# Rapide7seg.net
KiCad netlist of a schematic drawn in EAGLE
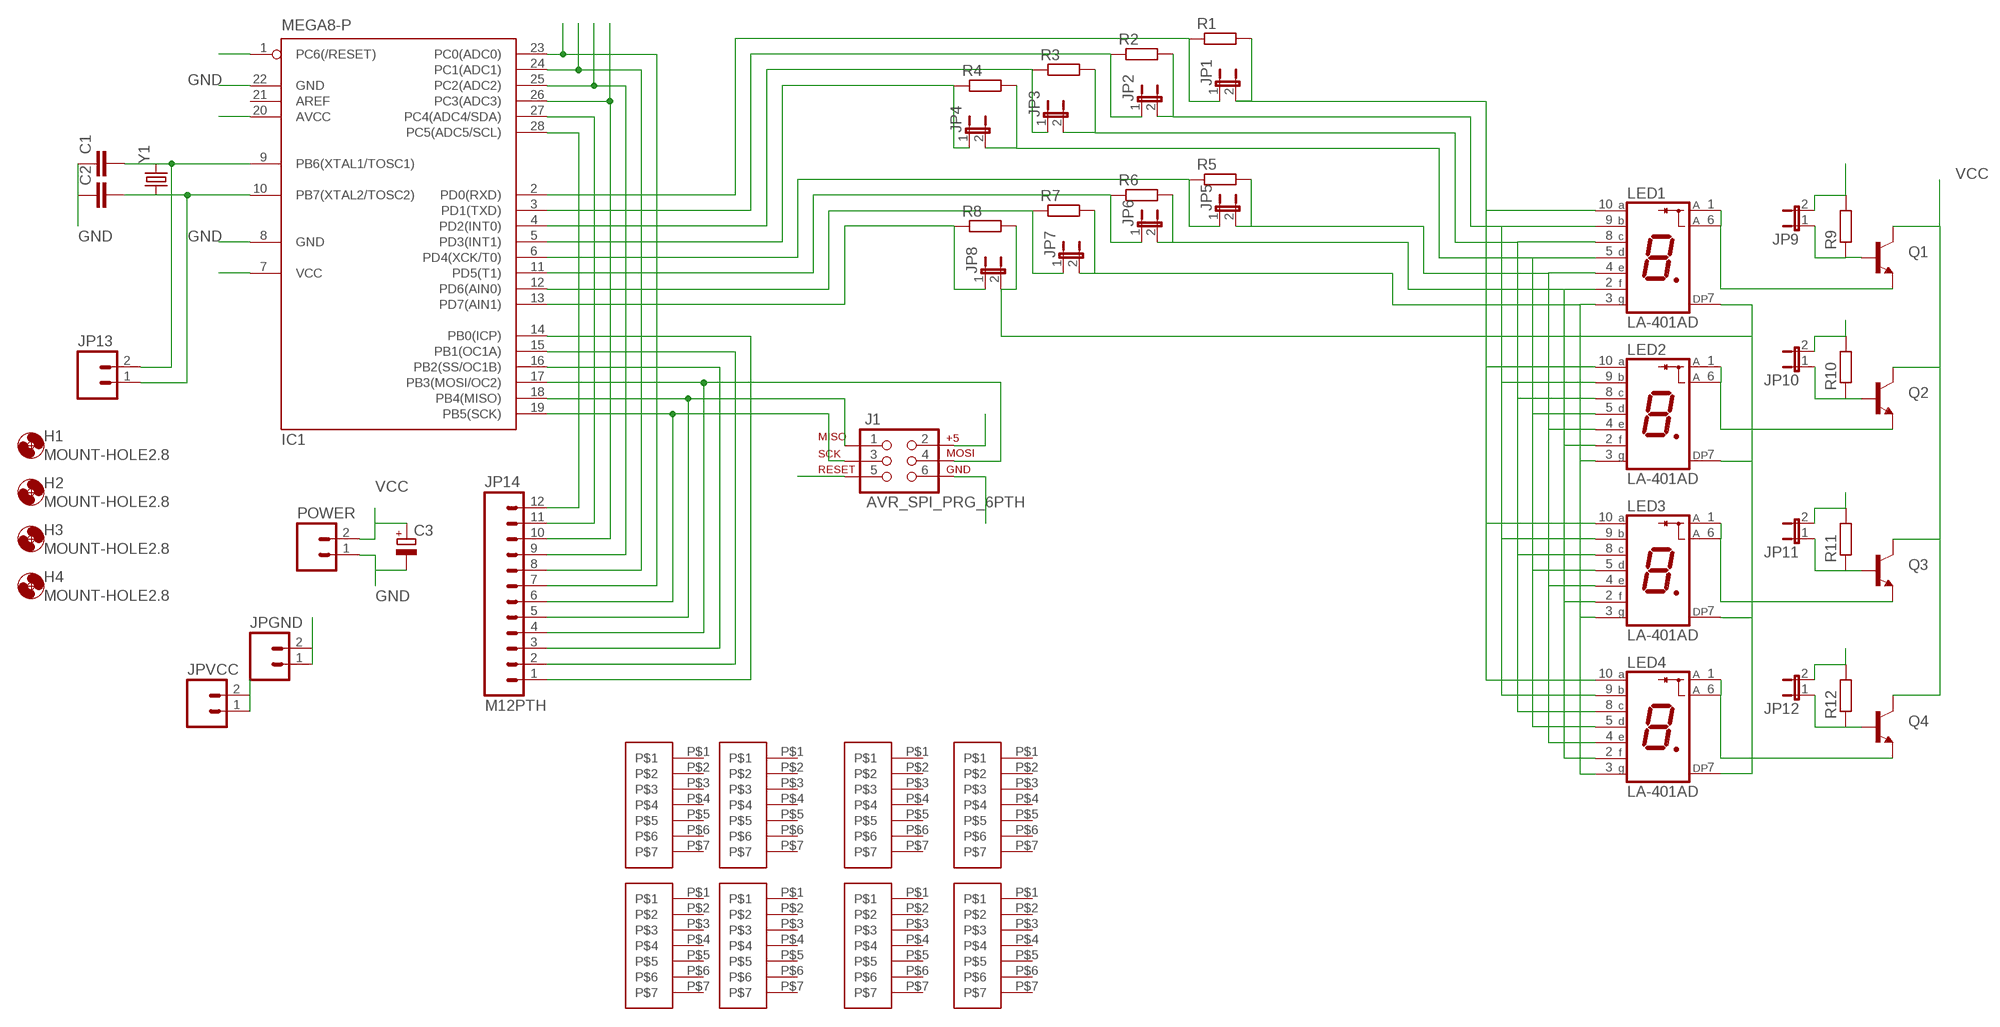
[diagram p0: schematic, sheet 1]

(export (version "E")
  (design (tool "Eeschema 10.0.6"))
  (components
    (comp (ref "C1")
      (value "C-EU025-024X044")
      (footprint "eagle-import:C025-024X044")
      (libsource (lib "eagle-import") (part "C-EU025-024X044"))
    )
    (comp (ref "C2")
      (value "C-EU025-024X044")
      (footprint "eagle-import:C025-024X044")
      (libsource (lib "eagle-import") (part "C-EU025-024X044"))
    )
    (comp (ref "C3")
      (value "CPOL-EUE1.8-4")
      (footprint "eagle-import:E1,8-4")
      (libsource (lib "eagle-import") (part "CPOL-EUE1.8-4"))
    )
    (comp (ref "H1")
      (value "MOUNT-HOLE2.8")
      (footprint "eagle-import:2,8")
      (libsource (lib "eagle-import") (part "MOUNT-HOLE2.8"))
    )
    (comp (ref "H2")
      (value "MOUNT-HOLE2.8")
      (footprint "eagle-import:2,8")
      (libsource (lib "eagle-import") (part "MOUNT-HOLE2.8"))
    )
    (comp (ref "H3")
      (value "MOUNT-HOLE2.8")
      (footprint "eagle-import:2,8")
      (libsource (lib "eagle-import") (part "MOUNT-HOLE2.8"))
    )
    (comp (ref "H4")
      (value "MOUNT-HOLE2.8")
      (footprint "eagle-import:2,8")
      (libsource (lib "eagle-import") (part "MOUNT-HOLE2.8"))
    )
    (comp (ref "IC1")
      (value "MEGA8-P")
      (footprint "eagle-import:DIL28-3")
      (libsource (lib "eagle-import") (part "MEGA8-P"))
    )
    (comp (ref "J1")
      (value "AVR_SPI_PRG_6PTH")
      (footprint "eagle-import:2X3")
      (libsource (lib "eagle-import") (part "AVR_SPI_PRG_6PTH"))
    )
    (comp (ref "JP1")
      (value "JUMPER-2SMD-NO")
      (footprint "eagle-import:SJ_2S-NO")
      (libsource (lib "eagle-import") (part "JUMPER-2SMD-NO"))
    )
    (comp (ref "JP2")
      (value "JUMPER-2SMD-NO")
      (footprint "eagle-import:SJ_2S-NO")
      (libsource (lib "eagle-import") (part "JUMPER-2SMD-NO"))
    )
    (comp (ref "JP3")
      (value "JUMPER-2SMD-NO")
      (footprint "eagle-import:SJ_2S-NO")
      (libsource (lib "eagle-import") (part "JUMPER-2SMD-NO"))
    )
    (comp (ref "JP4")
      (value "JUMPER-2SMD-NO")
      (footprint "eagle-import:SJ_2S-NO")
      (libsource (lib "eagle-import") (part "JUMPER-2SMD-NO"))
    )
    (comp (ref "JP5")
      (value "JUMPER-2SMD-NO")
      (footprint "eagle-import:SJ_2S-NO")
      (libsource (lib "eagle-import") (part "JUMPER-2SMD-NO"))
    )
    (comp (ref "JP6")
      (value "JUMPER-2SMD-NO")
      (footprint "eagle-import:SJ_2S-NO")
      (libsource (lib "eagle-import") (part "JUMPER-2SMD-NO"))
    )
    (comp (ref "JP7")
      (value "JUMPER-2SMD-NO")
      (footprint "eagle-import:SJ_2S-NO")
      (libsource (lib "eagle-import") (part "JUMPER-2SMD-NO"))
    )
    (comp (ref "JP8")
      (value "JUMPER-2SMD-NO")
      (footprint "eagle-import:SJ_2S-NO")
      (libsource (lib "eagle-import") (part "JUMPER-2SMD-NO"))
    )
    (comp (ref "JP9")
      (value "JUMPER-2SMD-NO")
      (footprint "eagle-import:SJ_2S-NO")
      (libsource (lib "eagle-import") (part "JUMPER-2SMD-NO"))
    )
    (comp (ref "JP10")
      (value "JUMPER-2SMD-NO")
      (footprint "eagle-import:SJ_2S-NO")
      (libsource (lib "eagle-import") (part "JUMPER-2SMD-NO"))
    )
    (comp (ref "JP11")
      (value "JUMPER-2SMD-NO")
      (footprint "eagle-import:SJ_2S-NO")
      (libsource (lib "eagle-import") (part "JUMPER-2SMD-NO"))
    )
    (comp (ref "JP12")
      (value "JUMPER-2SMD-NO")
      (footprint "eagle-import:SJ_2S-NO")
      (libsource (lib "eagle-import") (part "JUMPER-2SMD-NO"))
    )
    (comp (ref "JP13")
      (value "M02LOCK")
      (footprint "eagle-import:1X02_LOCK")
      (libsource (lib "eagle-import") (part "M02LOCK"))
    )
    (comp (ref "JP14")
      (value "M12PTH")
      (footprint "eagle-import:1X12")
      (libsource (lib "eagle-import") (part "M12PTH"))
    )
    (comp (ref "JPGND")
      (value "M02PTH")
      (footprint "eagle-import:1X02")
      (libsource (lib "eagle-import") (part "M02PTH"))
    )
    (comp (ref "JPVCC")
      (value "M02PTH")
      (footprint "eagle-import:1X02")
      (libsource (lib "eagle-import") (part "M02PTH"))
    )
    (comp (ref "LED1")
      (value "LA-401AD")
      (footprint "eagle-import:LA-401")
      (libsource (lib "eagle-import") (part "LA-401DA"))
    )
    (comp (ref "LED2")
      (value "LA-401AD")
      (footprint "eagle-import:LA-401")
      (libsource (lib "eagle-import") (part "LA-401DA"))
    )
    (comp (ref "LED3")
      (value "LA-401AD")
      (footprint "eagle-import:LA-401")
      (libsource (lib "eagle-import") (part "LA-401DA"))
    )
    (comp (ref "LED4")
      (value "LA-401AD")
      (footprint "eagle-import:LA-401")
      (libsource (lib "eagle-import") (part "LA-401DA"))
    )
    (comp (ref "POWER")
      (value "M02LOCK_LONGPADS")
      (footprint "eagle-import:1X02_LOCK_LONGPADS")
      (libsource (lib "eagle-import") (part "M02LOCK_LONGPADS"))
    )
    (comp (ref "Q1")
      (value "TRANSISTOR_NPNTO92")
      (footprint "eagle-import:TO-92")
      (libsource (lib "eagle-import") (part "TRANSISTOR_NPNTO92"))
    )
    (comp (ref "Q2")
      (value "TRANSISTOR_NPNTO92")
      (footprint "eagle-import:TO-92")
      (libsource (lib "eagle-import") (part "TRANSISTOR_NPNTO92"))
    )
    (comp (ref "Q3")
      (value "TRANSISTOR_NPNTO92")
      (footprint "eagle-import:TO-92")
      (libsource (lib "eagle-import") (part "TRANSISTOR_NPNTO92"))
    )
    (comp (ref "Q4")
      (value "TRANSISTOR_NPNTO92")
      (footprint "eagle-import:TO-92")
      (libsource (lib "eagle-import") (part "TRANSISTOR_NPNTO92"))
    )
    (comp (ref "R1")
      (value "R-EU_0204/7")
      (footprint "eagle-import:0204_7")
      (libsource (lib "eagle-import") (part "R-EU_0204/7"))
    )
    (comp (ref "R2")
      (value "R-EU_0204/7")
      (footprint "eagle-import:0204_7")
      (libsource (lib "eagle-import") (part "R-EU_0204/7"))
    )
    (comp (ref "R3")
      (value "R-EU_0204/7")
      (footprint "eagle-import:0204_7")
      (libsource (lib "eagle-import") (part "R-EU_0204/7"))
    )
    (comp (ref "R4")
      (value "R-EU_0204/7")
      (footprint "eagle-import:0204_7")
      (libsource (lib "eagle-import") (part "R-EU_0204/7"))
    )
    (comp (ref "R5")
      (value "R-EU_0204/7")
      (footprint "eagle-import:0204_7")
      (libsource (lib "eagle-import") (part "R-EU_0204/7"))
    )
    (comp (ref "R6")
      (value "R-EU_0204/7")
      (footprint "eagle-import:0204_7")
      (libsource (lib "eagle-import") (part "R-EU_0204/7"))
    )
    (comp (ref "R7")
      (value "R-EU_0204/7")
      (footprint "eagle-import:0204_7")
      (libsource (lib "eagle-import") (part "R-EU_0204/7"))
    )
    (comp (ref "R8")
      (value "R-EU_0204/7")
      (footprint "eagle-import:0204_7")
      (libsource (lib "eagle-import") (part "R-EU_0204/7"))
    )
    (comp (ref "R9")
      (value "R-EU_0204/7")
      (footprint "eagle-import:0204_7")
      (libsource (lib "eagle-import") (part "R-EU_0204/7"))
    )
    (comp (ref "R10")
      (value "R-EU_0204/7")
      (footprint "eagle-import:0204_7")
      (libsource (lib "eagle-import") (part "R-EU_0204/7"))
    )
    (comp (ref "R11")
      (value "R-EU_0204/7")
      (footprint "eagle-import:0204_7")
      (libsource (lib "eagle-import") (part "R-EU_0204/7"))
    )
    (comp (ref "R12")
      (value "R-EU_0204/7")
      (footprint "eagle-import:0204_7")
      (libsource (lib "eagle-import") (part "R-EU_0204/7"))
    )
    (comp (ref "U$1")
      (value "M7_NOSILK")
      (footprint "eagle-import:M7_NOSILK")
      (libsource (lib "eagle-import") (part "M7_NOSILK"))
    )
    (comp (ref "U$2")
      (value "M7_NOSILK")
      (footprint "eagle-import:M7_NOSILK")
      (libsource (lib "eagle-import") (part "M7_NOSILK"))
    )
    (comp (ref "U$3")
      (value "M7_NOSILK")
      (footprint "eagle-import:M7_NOSILK")
      (libsource (lib "eagle-import") (part "M7_NOSILK"))
    )
    (comp (ref "U$4")
      (value "M7_NOSILK")
      (footprint "eagle-import:M7_NOSILK")
      (libsource (lib "eagle-import") (part "M7_NOSILK"))
    )
    (comp (ref "U$5")
      (value "M7_NOSILK")
      (footprint "eagle-import:M7_NOSILK")
      (libsource (lib "eagle-import") (part "M7_NOSILK"))
    )
    (comp (ref "U$6")
      (value "M7_NOSILK")
      (footprint "eagle-import:M7_NOSILK")
      (libsource (lib "eagle-import") (part "M7_NOSILK"))
    )
    (comp (ref "U$7")
      (value "M7_NOSILK")
      (footprint "eagle-import:M7_NOSILK")
      (libsource (lib "eagle-import") (part "M7_NOSILK"))
    )
    (comp (ref "U$8")
      (value "M7_NOSILK")
      (footprint "eagle-import:M7_NOSILK")
      (libsource (lib "eagle-import") (part "M7_NOSILK"))
    )
    (comp (ref "Y1")
      (value "CRYSTALHC49UV")
      (footprint "eagle-import:HC49U-V")
      (libsource (lib "eagle-import") (part "CRYSTALHC49UV"))
    )
  )
  (nets
    (net (code "1") (name "/GND") (class "Default")
      (node (ref "C1") (pin "1") (pinfunction "1_1") (pintype "passive"))
      (node (ref "C2") (pin "1") (pinfunction "1_1") (pintype "passive"))
      (node (ref "C3") (pin "-") (pinfunction "-_-") (pintype "passive"))
      (node (ref "IC1") (pin "22") (pinfunction "GND_22") (pintype "power_in"))
      (node (ref "IC1") (pin "8") (pinfunction "GND_8") (pintype "power_in"))
      (node (ref "J1") (pin "6") (pinfunction "6_6") (pintype "passive"))
      (node (ref "JPGND") (pin "1") (pinfunction "1_1") (pintype "passive"))
      (node (ref "JPGND") (pin "2") (pinfunction "2_2") (pintype "passive"))
      (node (ref "POWER") (pin "1") (pinfunction "1_1") (pintype "passive"))
    )
    (net (code "2") (name "/L1") (class "Default")
      (node (ref "IC1") (pin "23") (pinfunction "PC0(ADC0)_23") (pintype "bidirectional"))
      (node (ref "JP14") (pin "7") (pinfunction "7_7") (pintype "passive"))
      (node (ref "JP9") (pin "2") (pinfunction "2_2") (pintype "passive"))
      (node (ref "R9") (pin "2") (pinfunction "2_2") (pintype "passive"))
    )
    (net (code "3") (name "/L2") (class "Default")
      (node (ref "IC1") (pin "24") (pinfunction "PC1(ADC1)_24") (pintype "bidirectional"))
      (node (ref "JP10") (pin "2") (pinfunction "2_2") (pintype "passive"))
      (node (ref "JP14") (pin "8") (pinfunction "8_8") (pintype "passive"))
      (node (ref "R10") (pin "2") (pinfunction "2_2") (pintype "passive"))
    )
    (net (code "4") (name "/L3") (class "Default")
      (node (ref "IC1") (pin "25") (pinfunction "PC2(ADC2)_25") (pintype "bidirectional"))
      (node (ref "JP11") (pin "2") (pinfunction "2_2") (pintype "passive"))
      (node (ref "JP14") (pin "9") (pinfunction "9_9") (pintype "passive"))
      (node (ref "R11") (pin "2") (pinfunction "2_2") (pintype "passive"))
    )
    (net (code "5") (name "/L4") (class "Default")
      (node (ref "IC1") (pin "26") (pinfunction "PC3(ADC3)_26") (pintype "bidirectional"))
      (node (ref "JP12") (pin "2") (pinfunction "2_2") (pintype "passive"))
      (node (ref "JP14") (pin "10") (pinfunction "10_10") (pintype "passive"))
      (node (ref "R12") (pin "2") (pinfunction "2_2") (pintype "passive"))
    )
    (net (code "6") (name "/UCRESET") (class "Default")
      (node (ref "IC1") (pin "1") (pinfunction "PC6(/RESET)_1") (pintype "bidirectional"))
      (node (ref "J1") (pin "5") (pinfunction "5_5") (pintype "passive"))
    )
    (net (code "7") (name "/VCC") (class "Default")
      (node (ref "C3") (pin "+") (pinfunction "+_+") (pintype "passive"))
      (node (ref "IC1") (pin "20") (pinfunction "AVCC_20") (pintype "power_in"))
      (node (ref "IC1") (pin "7") (pinfunction "VCC_7") (pintype "power_in"))
      (node (ref "J1") (pin "2") (pinfunction "2_2") (pintype "passive"))
      (node (ref "JPVCC") (pin "1") (pinfunction "1_1") (pintype "passive"))
      (node (ref "POWER") (pin "2") (pinfunction "2_2") (pintype "passive"))
      (node (ref "Q1") (pin "3") (pinfunction "C_3") (pintype "passive"))
      (node (ref "Q2") (pin "3") (pinfunction "C_3") (pintype "passive"))
      (node (ref "Q3") (pin "3") (pinfunction "C_3") (pintype "passive"))
      (node (ref "Q4") (pin "3") (pinfunction "C_3") (pintype "passive"))
    )
    (net (code "8") (name "Net-(IC1-PB0(ICP))") (class "Default")
      (node (ref "IC1") (pin "14") (pinfunction "PB0(ICP)_14") (pintype "bidirectional"))
      (node (ref "JP14") (pin "1") (pinfunction "1_1") (pintype "passive"))
    )
    (net (code "9") (name "Net-(IC1-PB1(OC1A))") (class "Default")
      (node (ref "IC1") (pin "15") (pinfunction "PB1(OC1A)_15") (pintype "bidirectional"))
      (node (ref "JP14") (pin "2") (pinfunction "2_2") (pintype "passive"))
    )
    (net (code "10") (name "Net-(IC1-PB2(SS{slash}OC1B))") (class "Default")
      (node (ref "IC1") (pin "16") (pinfunction "PB2(SS/OC1B)_16") (pintype "bidirectional"))
      (node (ref "JP14") (pin "3") (pinfunction "3_3") (pintype "passive"))
    )
    (net (code "11") (name "Net-(IC1-PB3(MOSI{slash}OC2))") (class "Default")
      (node (ref "IC1") (pin "17") (pinfunction "PB3(MOSI/OC2)_17") (pintype "bidirectional"))
      (node (ref "J1") (pin "4") (pinfunction "4_4") (pintype "passive"))
      (node (ref "JP14") (pin "4") (pinfunction "4_4") (pintype "passive"))
    )
    (net (code "12") (name "Net-(IC1-PB4(MISO))") (class "Default")
      (node (ref "IC1") (pin "18") (pinfunction "PB4(MISO)_18") (pintype "bidirectional"))
      (node (ref "J1") (pin "1") (pinfunction "1_1") (pintype "passive"))
      (node (ref "JP14") (pin "5") (pinfunction "5_5") (pintype "passive"))
    )
    (net (code "13") (name "Net-(IC1-PB5(SCK))") (class "Default")
      (node (ref "IC1") (pin "19") (pinfunction "PB5(SCK)_19") (pintype "bidirectional"))
      (node (ref "J1") (pin "3") (pinfunction "3_3") (pintype "passive"))
      (node (ref "JP14") (pin "6") (pinfunction "6_6") (pintype "passive"))
    )
    (net (code "14") (name "Net-(IC1-PB6(XTAL1{slash}TOSC1))") (class "Default")
      (node (ref "C1") (pin "2") (pinfunction "2_2") (pintype "passive"))
      (node (ref "IC1") (pin "9") (pinfunction "PB6(XTAL1/TOSC1)_9") (pintype "bidirectional"))
      (node (ref "JP13") (pin "2") (pinfunction "2_2") (pintype "passive"))
      (node (ref "Y1") (pin "2") (pinfunction "2_2") (pintype "passive"))
    )
    (net (code "15") (name "Net-(IC1-PB7(XTAL2{slash}TOSC2))") (class "Default")
      (node (ref "C2") (pin "2") (pinfunction "2_2") (pintype "passive"))
      (node (ref "IC1") (pin "10") (pinfunction "PB7(XTAL2/TOSC2)_10") (pintype "bidirectional"))
      (node (ref "JP13") (pin "1") (pinfunction "1_1") (pintype "passive"))
      (node (ref "Y1") (pin "1") (pinfunction "1_1") (pintype "passive"))
    )
    (net (code "16") (name "Net-(IC1-PC4(ADC4{slash}SDA))") (class "Default")
      (node (ref "IC1") (pin "27") (pinfunction "PC4(ADC4/SDA)_27") (pintype "bidirectional"))
      (node (ref "JP14") (pin "11") (pinfunction "11_11") (pintype "passive"))
    )
    (net (code "17") (name "Net-(IC1-PC5(ADC5{slash}SCL))") (class "Default")
      (node (ref "IC1") (pin "28") (pinfunction "PC5(ADC5/SCL)_28") (pintype "bidirectional"))
      (node (ref "JP14") (pin "12") (pinfunction "12_12") (pintype "passive"))
    )
    (net (code "18") (name "Net-(IC1-PD0(RXD))") (class "Default")
      (node (ref "IC1") (pin "2") (pinfunction "PD0(RXD)_2") (pintype "bidirectional"))
      (node (ref "JP1") (pin "1") (pinfunction "1_1") (pintype "passive"))
      (node (ref "R1") (pin "1") (pinfunction "1_1") (pintype "passive"))
    )
    (net (code "19") (name "Net-(IC1-PD1(TXD))") (class "Default")
      (node (ref "IC1") (pin "3") (pinfunction "PD1(TXD)_3") (pintype "bidirectional"))
      (node (ref "JP2") (pin "1") (pinfunction "1_1") (pintype "passive"))
      (node (ref "R2") (pin "1") (pinfunction "1_1") (pintype "passive"))
    )
    (net (code "20") (name "Net-(IC1-PD2(INT0))") (class "Default")
      (node (ref "IC1") (pin "4") (pinfunction "PD2(INT0)_4") (pintype "bidirectional"))
      (node (ref "JP3") (pin "1") (pinfunction "1_1") (pintype "passive"))
      (node (ref "R3") (pin "1") (pinfunction "1_1") (pintype "passive"))
    )
    (net (code "21") (name "Net-(IC1-PD3(INT1))") (class "Default")
      (node (ref "IC1") (pin "5") (pinfunction "PD3(INT1)_5") (pintype "bidirectional"))
      (node (ref "JP4") (pin "1") (pinfunction "1_1") (pintype "passive"))
      (node (ref "R4") (pin "1") (pinfunction "1_1") (pintype "passive"))
    )
    (net (code "22") (name "Net-(IC1-PD4(XCK{slash}T0))") (class "Default")
      (node (ref "IC1") (pin "6") (pinfunction "PD4(XCK/T0)_6") (pintype "bidirectional"))
      (node (ref "JP5") (pin "1") (pinfunction "1_1") (pintype "passive"))
      (node (ref "R5") (pin "1") (pinfunction "1_1") (pintype "passive"))
    )
    (net (code "23") (name "Net-(IC1-PD5(T1))") (class "Default")
      (node (ref "IC1") (pin "11") (pinfunction "PD5(T1)_11") (pintype "bidirectional"))
      (node (ref "JP6") (pin "1") (pinfunction "1_1") (pintype "passive"))
      (node (ref "R6") (pin "1") (pinfunction "1_1") (pintype "passive"))
    )
    (net (code "24") (name "Net-(IC1-PD6(AIN0))") (class "Default")
      (node (ref "IC1") (pin "12") (pinfunction "PD6(AIN0)_12") (pintype "bidirectional"))
      (node (ref "JP7") (pin "1") (pinfunction "1_1") (pintype "passive"))
      (node (ref "R7") (pin "1") (pinfunction "1_1") (pintype "passive"))
    )
    (net (code "25") (name "Net-(IC1-PD7(AIN1))") (class "Default")
      (node (ref "IC1") (pin "13") (pinfunction "PD7(AIN1)_13") (pintype "bidirectional"))
      (node (ref "JP8") (pin "1") (pinfunction "1_1") (pintype "passive"))
      (node (ref "R8") (pin "1") (pinfunction "1_1") (pintype "passive"))
    )
    (net (code "26") (name "Net-(JP1-Pad2)") (class "Default")
      (node (ref "JP1") (pin "2") (pinfunction "2_2") (pintype "passive"))
      (node (ref "LED1") (pin "10") (pinfunction "A_10") (pintype "passive"))
      (node (ref "LED2") (pin "10") (pinfunction "A_10") (pintype "passive"))
      (node (ref "LED3") (pin "10") (pinfunction "A_10") (pintype "passive"))
      (node (ref "LED4") (pin "10") (pinfunction "A_10") (pintype "passive"))
      (node (ref "R1") (pin "2") (pinfunction "2_2") (pintype "passive"))
    )
    (net (code "27") (name "Net-(LED1-B)") (class "Default")
      (node (ref "JP2") (pin "2") (pinfunction "2_2") (pintype "passive"))
      (node (ref "LED1") (pin "9") (pinfunction "B_9") (pintype "passive"))
      (node (ref "LED2") (pin "9") (pinfunction "B_9") (pintype "passive"))
      (node (ref "LED3") (pin "9") (pinfunction "B_9") (pintype "passive"))
      (node (ref "LED4") (pin "9") (pinfunction "B_9") (pintype "passive"))
      (node (ref "R2") (pin "2") (pinfunction "2_2") (pintype "passive"))
    )
    (net (code "28") (name "Net-(LED1-C)") (class "Default")
      (node (ref "JP3") (pin "2") (pinfunction "2_2") (pintype "passive"))
      (node (ref "LED1") (pin "8") (pinfunction "C_8") (pintype "passive"))
      (node (ref "LED2") (pin "8") (pinfunction "C_8") (pintype "passive"))
      (node (ref "LED3") (pin "8") (pinfunction "C_8") (pintype "passive"))
      (node (ref "LED4") (pin "8") (pinfunction "C_8") (pintype "passive"))
      (node (ref "R3") (pin "2") (pinfunction "2_2") (pintype "passive"))
    )
    (net (code "29") (name "Net-(LED1-D)") (class "Default")
      (node (ref "JP4") (pin "2") (pinfunction "2_2") (pintype "passive"))
      (node (ref "LED1") (pin "5") (pinfunction "D_5") (pintype "passive"))
      (node (ref "LED2") (pin "5") (pinfunction "D_5") (pintype "passive"))
      (node (ref "LED3") (pin "5") (pinfunction "D_5") (pintype "passive"))
      (node (ref "LED4") (pin "5") (pinfunction "D_5") (pintype "passive"))
      (node (ref "R4") (pin "2") (pinfunction "2_2") (pintype "passive"))
    )
    (net (code "30") (name "Net-(LED1-DP)") (class "Default")
      (node (ref "JP8") (pin "2") (pinfunction "2_2") (pintype "passive"))
      (node (ref "LED1") (pin "7") (pinfunction "DP_7") (pintype "passive"))
      (node (ref "LED2") (pin "7") (pinfunction "DP_7") (pintype "passive"))
      (node (ref "LED3") (pin "7") (pinfunction "DP_7") (pintype "passive"))
      (node (ref "LED4") (pin "7") (pinfunction "DP_7") (pintype "passive"))
      (node (ref "R8") (pin "2") (pinfunction "2_2") (pintype "passive"))
    )
    (net (code "31") (name "Net-(LED1-E)") (class "Default")
      (node (ref "JP5") (pin "2") (pinfunction "2_2") (pintype "passive"))
      (node (ref "LED1") (pin "4") (pinfunction "E_4") (pintype "passive"))
      (node (ref "LED2") (pin "4") (pinfunction "E_4") (pintype "passive"))
      (node (ref "LED3") (pin "4") (pinfunction "E_4") (pintype "passive"))
      (node (ref "LED4") (pin "4") (pinfunction "E_4") (pintype "passive"))
      (node (ref "R5") (pin "2") (pinfunction "2_2") (pintype "passive"))
    )
    (net (code "32") (name "Net-(LED1-F)") (class "Default")
      (node (ref "JP6") (pin "2") (pinfunction "2_2") (pintype "passive"))
      (node (ref "LED1") (pin "2") (pinfunction "F_2") (pintype "passive"))
      (node (ref "LED2") (pin "2") (pinfunction "F_2") (pintype "passive"))
      (node (ref "LED3") (pin "2") (pinfunction "F_2") (pintype "passive"))
      (node (ref "LED4") (pin "2") (pinfunction "F_2") (pintype "passive"))
      (node (ref "R6") (pin "2") (pinfunction "2_2") (pintype "passive"))
    )
    (net (code "33") (name "Net-(LED1-G)") (class "Default")
      (node (ref "JP7") (pin "2") (pinfunction "2_2") (pintype "passive"))
      (node (ref "LED1") (pin "3") (pinfunction "G_3") (pintype "passive"))
      (node (ref "LED2") (pin "3") (pinfunction "G_3") (pintype "passive"))
      (node (ref "LED3") (pin "3") (pinfunction "G_3") (pintype "passive"))
      (node (ref "LED4") (pin "3") (pinfunction "G_3") (pintype "passive"))
      (node (ref "R7") (pin "2") (pinfunction "2_2") (pintype "passive"))
    )
    (net (code "34") (name "Net-(Q1-B)") (class "Default")
      (node (ref "JP9") (pin "1") (pinfunction "1_1") (pintype "passive"))
      (node (ref "Q1") (pin "2") (pinfunction "B_2") (pintype "passive"))
      (node (ref "R9") (pin "1") (pinfunction "1_1") (pintype "passive"))
    )
    (net (code "35") (name "Net-(Q1-E)") (class "Default")
      (node (ref "LED1") (pin "1") (pinfunction "A_1") (pintype "passive"))
      (node (ref "LED1") (pin "6") (pinfunction "A_6") (pintype "passive"))
      (node (ref "Q1") (pin "1") (pinfunction "E_1") (pintype "passive"))
    )
    (net (code "36") (name "Net-(Q2-B)") (class "Default")
      (node (ref "JP10") (pin "1") (pinfunction "1_1") (pintype "passive"))
      (node (ref "Q2") (pin "2") (pinfunction "B_2") (pintype "passive"))
      (node (ref "R10") (pin "1") (pinfunction "1_1") (pintype "passive"))
    )
    (net (code "37") (name "Net-(Q2-E)") (class "Default")
      (node (ref "LED2") (pin "1") (pinfunction "A_1") (pintype "passive"))
      (node (ref "LED2") (pin "6") (pinfunction "A_6") (pintype "passive"))
      (node (ref "Q2") (pin "1") (pinfunction "E_1") (pintype "passive"))
    )
    (net (code "38") (name "Net-(Q3-B)") (class "Default")
      (node (ref "JP11") (pin "1") (pinfunction "1_1") (pintype "passive"))
      (node (ref "Q3") (pin "2") (pinfunction "B_2") (pintype "passive"))
      (node (ref "R11") (pin "1") (pinfunction "1_1") (pintype "passive"))
    )
    (net (code "39") (name "Net-(Q3-E)") (class "Default")
      (node (ref "LED3") (pin "1") (pinfunction "A_1") (pintype "passive"))
      (node (ref "LED3") (pin "6") (pinfunction "A_6") (pintype "passive"))
      (node (ref "Q3") (pin "1") (pinfunction "E_1") (pintype "passive"))
    )
    (net (code "40") (name "Net-(Q4-B)") (class "Default")
      (node (ref "JP12") (pin "1") (pinfunction "1_1") (pintype "passive"))
      (node (ref "Q4") (pin "2") (pinfunction "B_2") (pintype "passive"))
      (node (ref "R12") (pin "1") (pinfunction "1_1") (pintype "passive"))
    )
    (net (code "41") (name "Net-(Q4-E)") (class "Default")
      (node (ref "LED4") (pin "1") (pinfunction "A_1") (pintype "passive"))
      (node (ref "LED4") (pin "6") (pinfunction "A_6") (pintype "passive"))
      (node (ref "Q4") (pin "1") (pinfunction "E_1") (pintype "passive"))
    )
    (net (code "42") (name "unconnected-(IC1-AREF-Pad21)") (class "Default")
      (node (ref "IC1") (pin "21") (pinfunction "AREF_21") (pintype "passive"))
    )
    (net (code "43") (name "unconnected-(JPVCC-Pad2)") (class "Default")
      (node (ref "JPVCC") (pin "2") (pinfunction "2_2") (pintype "passive"))
    )
    (net (code "44") (name "unconnected-(U$1-PadP$1)") (class "Default")
      (node (ref "U$1") (pin "P$1") (pinfunction "P$1_P$1") (pintype "bidirectional"))
    )
    (net (code "45") (name "unconnected-(U$1-PadP$2)") (class "Default")
      (node (ref "U$1") (pin "P$2") (pinfunction "P$2_P$2") (pintype "bidirectional"))
    )
    (net (code "46") (name "unconnected-(U$1-PadP$3)") (class "Default")
      (node (ref "U$1") (pin "P$3") (pinfunction "P$3_P$3") (pintype "bidirectional"))
    )
    (net (code "47") (name "unconnected-(U$1-PadP$4)") (class "Default")
      (node (ref "U$1") (pin "P$4") (pinfunction "P$4_P$4") (pintype "bidirectional"))
    )
    (net (code "48") (name "unconnected-(U$1-PadP$5)") (class "Default")
      (node (ref "U$1") (pin "P$5") (pinfunction "P$5_P$5") (pintype "bidirectional"))
    )
    (net (code "49") (name "unconnected-(U$1-PadP$6)") (class "Default")
      (node (ref "U$1") (pin "P$6") (pinfunction "P$6_P$6") (pintype "bidirectional"))
    )
    (net (code "50") (name "unconnected-(U$1-PadP$7)") (class "Default")
      (node (ref "U$1") (pin "P$7") (pinfunction "P$7_P$7") (pintype "bidirectional"))
    )
    (net (code "51") (name "unconnected-(U$2-PadP$1)") (class "Default")
      (node (ref "U$2") (pin "P$1") (pinfunction "P$1_P$1") (pintype "bidirectional"))
    )
    (net (code "52") (name "unconnected-(U$2-PadP$2)") (class "Default")
      (node (ref "U$2") (pin "P$2") (pinfunction "P$2_P$2") (pintype "bidirectional"))
    )
    (net (code "53") (name "unconnected-(U$2-PadP$3)") (class "Default")
      (node (ref "U$2") (pin "P$3") (pinfunction "P$3_P$3") (pintype "bidirectional"))
    )
    (net (code "54") (name "unconnected-(U$2-PadP$4)") (class "Default")
      (node (ref "U$2") (pin "P$4") (pinfunction "P$4_P$4") (pintype "bidirectional"))
    )
    (net (code "55") (name "unconnected-(U$2-PadP$5)") (class "Default")
      (node (ref "U$2") (pin "P$5") (pinfunction "P$5_P$5") (pintype "bidirectional"))
    )
    (net (code "56") (name "unconnected-(U$2-PadP$6)") (class "Default")
      (node (ref "U$2") (pin "P$6") (pinfunction "P$6_P$6") (pintype "bidirectional"))
    )
    (net (code "57") (name "unconnected-(U$2-PadP$7)") (class "Default")
      (node (ref "U$2") (pin "P$7") (pinfunction "P$7_P$7") (pintype "bidirectional"))
    )
    (net (code "58") (name "unconnected-(U$3-PadP$1)") (class "Default")
      (node (ref "U$3") (pin "P$1") (pinfunction "P$1_P$1") (pintype "bidirectional"))
    )
    (net (code "59") (name "unconnected-(U$3-PadP$2)") (class "Default")
      (node (ref "U$3") (pin "P$2") (pinfunction "P$2_P$2") (pintype "bidirectional"))
    )
    (net (code "60") (name "unconnected-(U$3-PadP$3)") (class "Default")
      (node (ref "U$3") (pin "P$3") (pinfunction "P$3_P$3") (pintype "bidirectional"))
    )
    (net (code "61") (name "unconnected-(U$3-PadP$4)") (class "Default")
      (node (ref "U$3") (pin "P$4") (pinfunction "P$4_P$4") (pintype "bidirectional"))
    )
    (net (code "62") (name "unconnected-(U$3-PadP$5)") (class "Default")
      (node (ref "U$3") (pin "P$5") (pinfunction "P$5_P$5") (pintype "bidirectional"))
    )
    (net (code "63") (name "unconnected-(U$3-PadP$6)") (class "Default")
      (node (ref "U$3") (pin "P$6") (pinfunction "P$6_P$6") (pintype "bidirectional"))
    )
    (net (code "64") (name "unconnected-(U$3-PadP$7)") (class "Default")
      (node (ref "U$3") (pin "P$7") (pinfunction "P$7_P$7") (pintype "bidirectional"))
    )
    (net (code "65") (name "unconnected-(U$4-PadP$1)") (class "Default")
      (node (ref "U$4") (pin "P$1") (pinfunction "P$1_P$1") (pintype "bidirectional"))
    )
    (net (code "66") (name "unconnected-(U$4-PadP$2)") (class "Default")
      (node (ref "U$4") (pin "P$2") (pinfunction "P$2_P$2") (pintype "bidirectional"))
    )
    (net (code "67") (name "unconnected-(U$4-PadP$3)") (class "Default")
      (node (ref "U$4") (pin "P$3") (pinfunction "P$3_P$3") (pintype "bidirectional"))
    )
    (net (code "68") (name "unconnected-(U$4-PadP$4)") (class "Default")
      (node (ref "U$4") (pin "P$4") (pinfunction "P$4_P$4") (pintype "bidirectional"))
    )
    (net (code "69") (name "unconnected-(U$4-PadP$5)") (class "Default")
      (node (ref "U$4") (pin "P$5") (pinfunction "P$5_P$5") (pintype "bidirectional"))
    )
    (net (code "70") (name "unconnected-(U$4-PadP$6)") (class "Default")
      (node (ref "U$4") (pin "P$6") (pinfunction "P$6_P$6") (pintype "bidirectional"))
    )
    (net (code "71") (name "unconnected-(U$4-PadP$7)") (class "Default")
      (node (ref "U$4") (pin "P$7") (pinfunction "P$7_P$7") (pintype "bidirectional"))
    )
    (net (code "72") (name "unconnected-(U$5-PadP$1)") (class "Default")
      (node (ref "U$5") (pin "P$1") (pinfunction "P$1_P$1") (pintype "bidirectional"))
    )
    (net (code "73") (name "unconnected-(U$5-PadP$2)") (class "Default")
      (node (ref "U$5") (pin "P$2") (pinfunction "P$2_P$2") (pintype "bidirectional"))
    )
    (net (code "74") (name "unconnected-(U$5-PadP$3)") (class "Default")
      (node (ref "U$5") (pin "P$3") (pinfunction "P$3_P$3") (pintype "bidirectional"))
    )
    (net (code "75") (name "unconnected-(U$5-PadP$4)") (class "Default")
      (node (ref "U$5") (pin "P$4") (pinfunction "P$4_P$4") (pintype "bidirectional"))
    )
    (net (code "76") (name "unconnected-(U$5-PadP$5)") (class "Default")
      (node (ref "U$5") (pin "P$5") (pinfunction "P$5_P$5") (pintype "bidirectional"))
    )
    (net (code "77") (name "unconnected-(U$5-PadP$6)") (class "Default")
      (node (ref "U$5") (pin "P$6") (pinfunction "P$6_P$6") (pintype "bidirectional"))
    )
    (net (code "78") (name "unconnected-(U$5-PadP$7)") (class "Default")
      (node (ref "U$5") (pin "P$7") (pinfunction "P$7_P$7") (pintype "bidirectional"))
    )
    (net (code "79") (name "unconnected-(U$6-PadP$1)") (class "Default")
      (node (ref "U$6") (pin "P$1") (pinfunction "P$1_P$1") (pintype "bidirectional"))
    )
    (net (code "80") (name "unconnected-(U$6-PadP$2)") (class "Default")
      (node (ref "U$6") (pin "P$2") (pinfunction "P$2_P$2") (pintype "bidirectional"))
    )
    (net (code "81") (name "unconnected-(U$6-PadP$3)") (class "Default")
      (node (ref "U$6") (pin "P$3") (pinfunction "P$3_P$3") (pintype "bidirectional"))
    )
    (net (code "82") (name "unconnected-(U$6-PadP$4)") (class "Default")
      (node (ref "U$6") (pin "P$4") (pinfunction "P$4_P$4") (pintype "bidirectional"))
    )
    (net (code "83") (name "unconnected-(U$6-PadP$5)") (class "Default")
      (node (ref "U$6") (pin "P$5") (pinfunction "P$5_P$5") (pintype "bidirectional"))
    )
    (net (code "84") (name "unconnected-(U$6-PadP$6)") (class "Default")
      (node (ref "U$6") (pin "P$6") (pinfunction "P$6_P$6") (pintype "bidirectional"))
    )
    (net (code "85") (name "unconnected-(U$6-PadP$7)") (class "Default")
      (node (ref "U$6") (pin "P$7") (pinfunction "P$7_P$7") (pintype "bidirectional"))
    )
    (net (code "86") (name "unconnected-(U$7-PadP$1)") (class "Default")
      (node (ref "U$7") (pin "P$1") (pinfunction "P$1_P$1") (pintype "bidirectional"))
    )
    (net (code "87") (name "unconnected-(U$7-PadP$2)") (class "Default")
      (node (ref "U$7") (pin "P$2") (pinfunction "P$2_P$2") (pintype "bidirectional"))
    )
    (net (code "88") (name "unconnected-(U$7-PadP$3)") (class "Default")
      (node (ref "U$7") (pin "P$3") (pinfunction "P$3_P$3") (pintype "bidirectional"))
    )
    (net (code "89") (name "unconnected-(U$7-PadP$4)") (class "Default")
      (node (ref "U$7") (pin "P$4") (pinfunction "P$4_P$4") (pintype "bidirectional"))
    )
    (net (code "90") (name "unconnected-(U$7-PadP$5)") (class "Default")
      (node (ref "U$7") (pin "P$5") (pinfunction "P$5_P$5") (pintype "bidirectional"))
    )
    (net (code "91") (name "unconnected-(U$7-PadP$6)") (class "Default")
      (node (ref "U$7") (pin "P$6") (pinfunction "P$6_P$6") (pintype "bidirectional"))
    )
    (net (code "92") (name "unconnected-(U$7-PadP$7)") (class "Default")
      (node (ref "U$7") (pin "P$7") (pinfunction "P$7_P$7") (pintype "bidirectional"))
    )
    (net (code "93") (name "unconnected-(U$8-PadP$1)") (class "Default")
      (node (ref "U$8") (pin "P$1") (pinfunction "P$1_P$1") (pintype "bidirectional"))
    )
    (net (code "94") (name "unconnected-(U$8-PadP$2)") (class "Default")
      (node (ref "U$8") (pin "P$2") (pinfunction "P$2_P$2") (pintype "bidirectional"))
    )
    (net (code "95") (name "unconnected-(U$8-PadP$3)") (class "Default")
      (node (ref "U$8") (pin "P$3") (pinfunction "P$3_P$3") (pintype "bidirectional"))
    )
    (net (code "96") (name "unconnected-(U$8-PadP$4)") (class "Default")
      (node (ref "U$8") (pin "P$4") (pinfunction "P$4_P$4") (pintype "bidirectional"))
    )
    (net (code "97") (name "unconnected-(U$8-PadP$5)") (class "Default")
      (node (ref "U$8") (pin "P$5") (pinfunction "P$5_P$5") (pintype "bidirectional"))
    )
    (net (code "98") (name "unconnected-(U$8-PadP$6)") (class "Default")
      (node (ref "U$8") (pin "P$6") (pinfunction "P$6_P$6") (pintype "bidirectional"))
    )
    (net (code "99") (name "unconnected-(U$8-PadP$7)") (class "Default")
      (node (ref "U$8") (pin "P$7") (pinfunction "P$7_P$7") (pintype "bidirectional"))
    )
  )
)
